# commonBoard.net
KiCad netlist of a schematic drawn in EAGLE
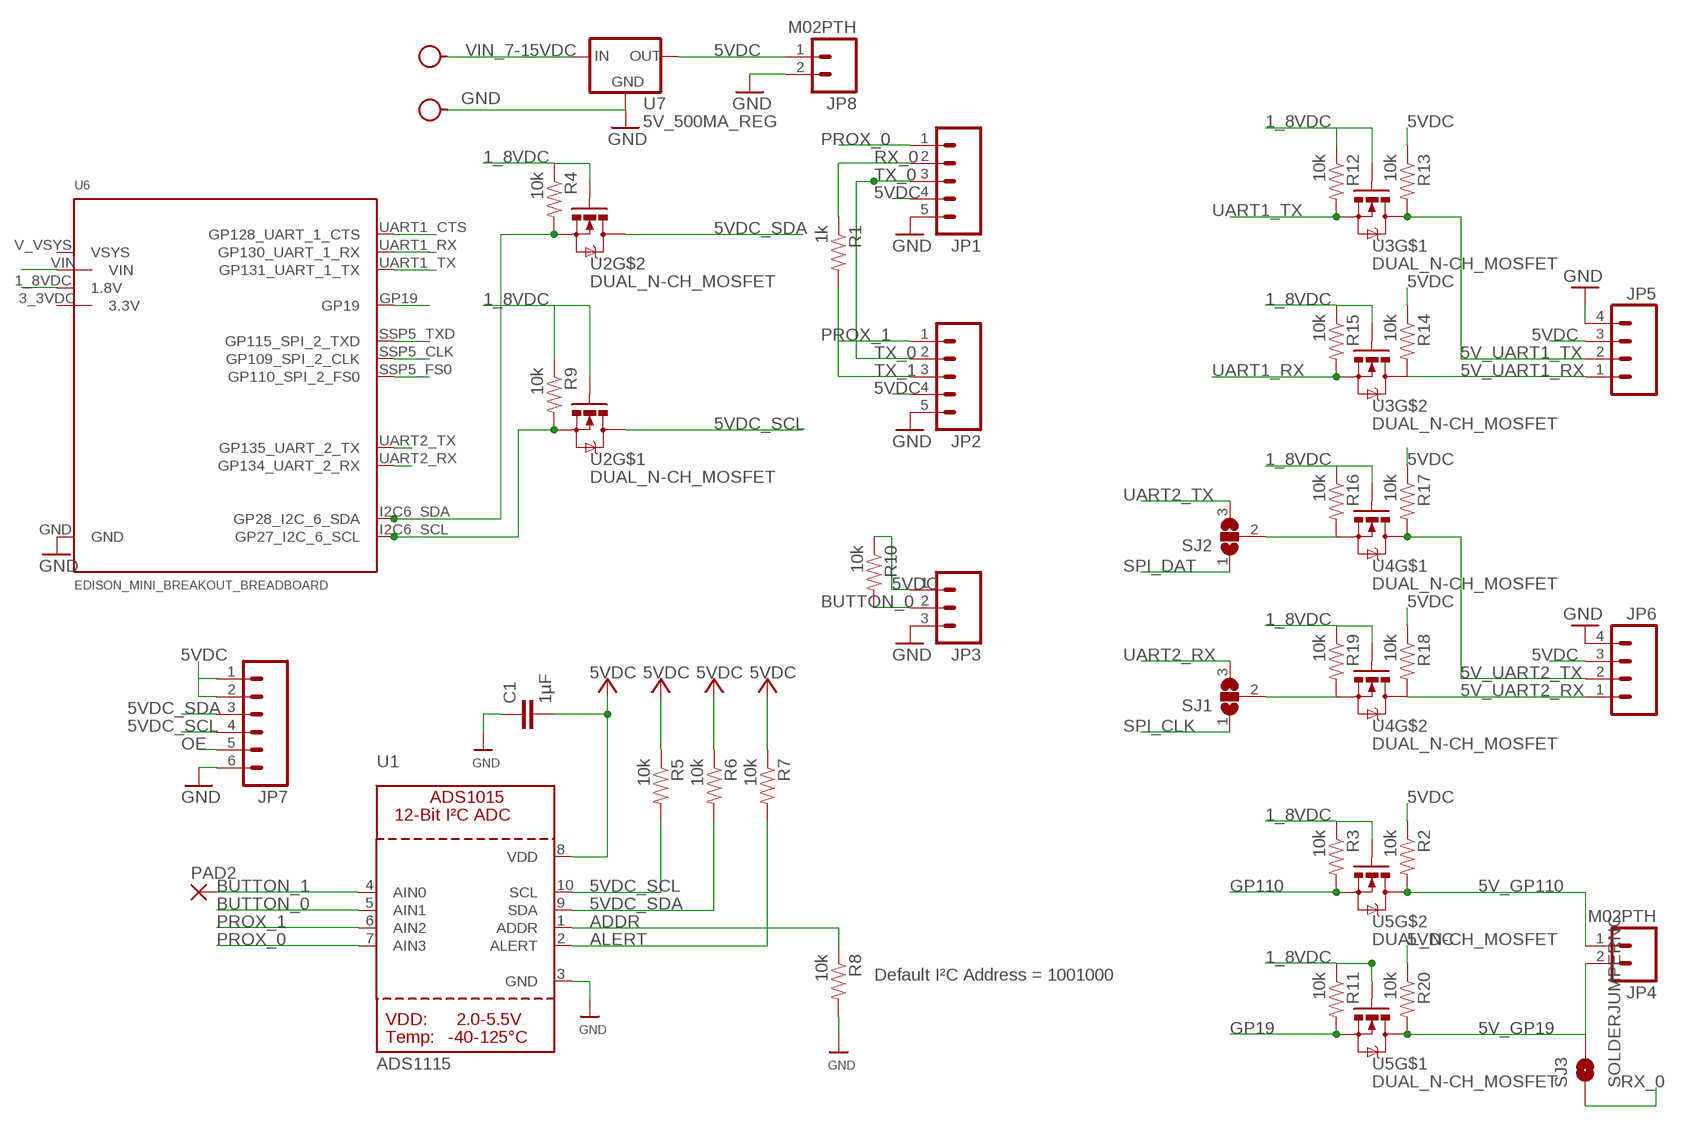
[diagram p0: schematic, sheet 1]

(export (version "E")
  (design (tool "Eeschema 10.0.6"))
  (components
    (comp (ref "C1")
      (value "1µF")
      (footprint "eagle-import:0603-CAP")
      (libsource (lib "eagle-import") (part "CAP0603-CAP"))
    )
    (comp (ref "GND")
      (value "SEW_HOLE-SMALL")
      (footprint "eagle-import:SIMPLE_HOLE_SM")
      (libsource (lib "eagle-import") (part "SEW_HOLE-SMALL"))
    )
    (comp (ref "JP1")
      (value "M05PTH")
      (footprint "eagle-import:1X05")
      (libsource (lib "eagle-import") (part "M05PTH"))
    )
    (comp (ref "JP2")
      (value "M05PTH")
      (footprint "eagle-import:1X05")
      (libsource (lib "eagle-import") (part "M05PTH"))
    )
    (comp (ref "JP3")
      (value "M03PTH")
      (footprint "eagle-import:1X03")
      (libsource (lib "eagle-import") (part "M03PTH"))
    )
    (comp (ref "JP4")
      (value "M02PTH")
      (footprint "eagle-import:1X02")
      (libsource (lib "eagle-import") (part "M02PTH"))
    )
    (comp (ref "JP5")
      (value "M04PTH")
      (footprint "eagle-import:1X04")
      (libsource (lib "eagle-import") (part "M04PTH"))
    )
    (comp (ref "JP6")
      (value "M04PTH")
      (footprint "eagle-import:1X04")
      (libsource (lib "eagle-import") (part "M04PTH"))
    )
    (comp (ref "JP7")
      (value "M06SIP")
      (footprint "eagle-import:1X06")
      (libsource (lib "eagle-import") (part "M06SIP"))
    )
    (comp (ref "JP8")
      (value "M02PTH")
      (footprint "eagle-import:1X02")
      (libsource (lib "eagle-import") (part "M02PTH"))
    )
    (comp (ref "PAD2")
      (value "2,15/1,0")
      (footprint "eagle-import:2,15_1,0")
      (libsource (lib "eagle-import") (part "2,15/1,0"))
    )
    (comp (ref "R1")
      (value "1k")
      (footprint "eagle-import:0603-RES")
      (libsource (lib "eagle-import") (part "RESISTOR0603-RES"))
    )
    (comp (ref "R2")
      (value "10k")
      (footprint "eagle-import:0603-RES")
      (libsource (lib "eagle-import") (part "RESISTOR0603-RES"))
    )
    (comp (ref "R3")
      (value "10k")
      (footprint "eagle-import:0603-RES")
      (libsource (lib "eagle-import") (part "RESISTOR0603-RES"))
    )
    (comp (ref "R4")
      (value "10k")
      (footprint "eagle-import:0603-RES")
      (libsource (lib "eagle-import") (part "RESISTOR0603-RES"))
    )
    (comp (ref "R5")
      (value "10k")
      (footprint "eagle-import:0603-RES")
      (libsource (lib "eagle-import") (part "RESISTOR0603-RES"))
    )
    (comp (ref "R6")
      (value "10k")
      (footprint "eagle-import:0603-RES")
      (libsource (lib "eagle-import") (part "RESISTOR0603-RES"))
    )
    (comp (ref "R7")
      (value "10k")
      (footprint "eagle-import:0603-RES")
      (libsource (lib "eagle-import") (part "RESISTOR0603-RES"))
    )
    (comp (ref "R8")
      (value "10k")
      (footprint "eagle-import:0603-RES")
      (libsource (lib "eagle-import") (part "RESISTOR0603-RES"))
    )
    (comp (ref "R9")
      (value "10k")
      (footprint "eagle-import:0603-RES")
      (libsource (lib "eagle-import") (part "RESISTOR0603-RES"))
    )
    (comp (ref "R10")
      (value "10k")
      (footprint "eagle-import:0603-RES")
      (libsource (lib "eagle-import") (part "RESISTOR0603-RES"))
    )
    (comp (ref "R11")
      (value "10k")
      (footprint "eagle-import:0603-RES")
      (libsource (lib "eagle-import") (part "RESISTOR0603-RES"))
    )
    (comp (ref "R12")
      (value "10k")
      (footprint "eagle-import:0603-RES")
      (libsource (lib "eagle-import") (part "RESISTOR0603-RES"))
    )
    (comp (ref "R13")
      (value "10k")
      (footprint "eagle-import:0603-RES")
      (libsource (lib "eagle-import") (part "RESISTOR0603-RES"))
    )
    (comp (ref "R14")
      (value "10k")
      (footprint "eagle-import:0603-RES")
      (libsource (lib "eagle-import") (part "RESISTOR0603-RES"))
    )
    (comp (ref "R15")
      (value "10k")
      (footprint "eagle-import:0603-RES")
      (libsource (lib "eagle-import") (part "RESISTOR0603-RES"))
    )
    (comp (ref "R16")
      (value "10k")
      (footprint "eagle-import:0603-RES")
      (libsource (lib "eagle-import") (part "RESISTOR0603-RES"))
    )
    (comp (ref "R17")
      (value "10k")
      (footprint "eagle-import:0603-RES")
      (libsource (lib "eagle-import") (part "RESISTOR0603-RES"))
    )
    (comp (ref "R18")
      (value "10k")
      (footprint "eagle-import:0603-RES")
      (libsource (lib "eagle-import") (part "RESISTOR0603-RES"))
    )
    (comp (ref "R19")
      (value "10k")
      (footprint "eagle-import:0603-RES")
      (libsource (lib "eagle-import") (part "RESISTOR0603-RES"))
    )
    (comp (ref "R20")
      (value "10k")
      (footprint "eagle-import:0603-RES")
      (libsource (lib "eagle-import") (part "RESISTOR0603-RES"))
    )
    (comp (ref "SJ1")
      (value "SJ2W")
      (footprint "eagle-import:SJ_2")
      (libsource (lib "eagle-import") (part "SJ2W"))
    )
    (comp (ref "SJ2")
      (value "SJ2W")
      (footprint "eagle-import:SJ_2")
      (libsource (lib "eagle-import") (part "SJ2W"))
    )
    (comp (ref "SJ3")
      (value "SOLDERJUMPERNC")
      (footprint "eagle-import:SJ_2S")
      (libsource (lib "eagle-import") (part "SOLDERJUMPERNC"))
    )
    (comp (ref "U1")
      (value "ADS1115")
      (footprint "eagle-import:MSOP10")
      (libsource (lib "eagle-import") (part "ADC_ADS1015"))
    )
    (comp (ref "U2")
      (value "DUAL_N-CH_MOSFET")
      (footprint "eagle-import:SOT363_DUAL_N_MOSFET")
      (libsource (lib "eagle-import") (part "DUAL_N-CH_MOSFET"))
    )
    (comp (ref "U3")
      (value "DUAL_N-CH_MOSFET")
      (footprint "eagle-import:SOT363_DUAL_N_MOSFET")
      (libsource (lib "eagle-import") (part "DUAL_N-CH_MOSFET"))
    )
    (comp (ref "U4")
      (value "DUAL_N-CH_MOSFET")
      (footprint "eagle-import:SOT363_DUAL_N_MOSFET")
      (libsource (lib "eagle-import") (part "DUAL_N-CH_MOSFET"))
    )
    (comp (ref "U5")
      (value "DUAL_N-CH_MOSFET")
      (footprint "eagle-import:SOT363_DUAL_N_MOSFET")
      (libsource (lib "eagle-import") (part "DUAL_N-CH_MOSFET"))
    )
    (comp (ref "U6")
      (value "EDISON_MINI_BREAKOUT_BREADBOARD")
      (footprint "eagle-import:EDISON_MINI_BREAK_BREADBOARD")
      (libsource (lib "eagle-import") (part "EDISON_MINI_BREAKOUT_BREADBOARD"))
    )
    (comp (ref "U7")
      (value "5V_500MA_REG")
      (footprint "eagle-import:5V_500MA_REG")
      (libsource (lib "eagle-import") (part "5V_500MA_REG"))
    )
    (comp (ref "VIN_7-15VDC")
      (value "SEW_HOLE-SMALL")
      (footprint "eagle-import:SIMPLE_HOLE_SM")
      (libsource (lib "eagle-import") (part "SEW_HOLE-SMALL"))
    )
  )
  (nets
    (net (code "1") (name "/1_8VDC") (class "Default")
      (node (ref "R11") (pin "1") (pinfunction "1_1") (pintype "passive"))
      (node (ref "R12") (pin "1") (pinfunction "1_1") (pintype "passive"))
      (node (ref "R15") (pin "1") (pinfunction "1_1") (pintype "passive"))
      (node (ref "R16") (pin "1") (pinfunction "1_1") (pintype "passive"))
      (node (ref "R19") (pin "1") (pinfunction "1_1") (pintype "passive"))
      (node (ref "R3") (pin "1") (pinfunction "1_1") (pintype "passive"))
      (node (ref "R4") (pin "1") (pinfunction "1_1") (pintype "passive"))
      (node (ref "R9") (pin "1") (pinfunction "1_1") (pintype "passive"))
      (node (ref "U2") (pin "2") (pinfunction "G_2") (pintype "passive"))
      (node (ref "U2") (pin "5") (pinfunction "G_5") (pintype "passive"))
      (node (ref "U3") (pin "2") (pinfunction "G_2") (pintype "passive"))
      (node (ref "U3") (pin "5") (pinfunction "G_5") (pintype "passive"))
      (node (ref "U4") (pin "2") (pinfunction "G_2") (pintype "passive"))
      (node (ref "U4") (pin "5") (pinfunction "G_5") (pintype "passive"))
      (node (ref "U5") (pin "2") (pinfunction "G_2") (pintype "passive"))
      (node (ref "U5") (pin "5") (pinfunction "G_5") (pintype "passive"))
      (node (ref "U6") (pin "1_8VDC") (pinfunction "1.8V_1_8VDC") (pintype "bidirectional"))
    )
    (net (code "2") (name "/5VDC_SCL") (class "Default")
      (node (ref "JP7") (pin "4") (pinfunction "4_4") (pintype "passive"))
      (node (ref "R5") (pin "2") (pinfunction "2_2") (pintype "passive"))
      (node (ref "U1") (pin "10") (pinfunction "SCL_10") (pintype "bidirectional"))
      (node (ref "U2") (pin "3") (pinfunction "D_3") (pintype "passive"))
    )
    (net (code "3") (name "/5VDC_SDA") (class "Default")
      (node (ref "JP7") (pin "3") (pinfunction "3_3") (pintype "passive"))
      (node (ref "R6") (pin "2") (pinfunction "2_2") (pintype "passive"))
      (node (ref "U1") (pin "9") (pinfunction "SDA_9") (pintype "bidirectional"))
      (node (ref "U2") (pin "6") (pinfunction "D_6") (pintype "passive"))
    )
    (net (code "4") (name "/5V_GP19") (class "Default")
      (node (ref "JP4") (pin "2") (pinfunction "2_2") (pintype "passive"))
      (node (ref "R20") (pin "2") (pinfunction "2_2") (pintype "passive"))
      (node (ref "SJ3") (pin "2") (pinfunction "2_2") (pintype "passive"))
      (node (ref "U5") (pin "3") (pinfunction "D_3") (pintype "passive"))
    )
    (net (code "5") (name "/5V_GP110") (class "Default")
      (node (ref "JP4") (pin "1") (pinfunction "1_1") (pintype "passive"))
      (node (ref "R2") (pin "2") (pinfunction "2_2") (pintype "passive"))
      (node (ref "U5") (pin "6") (pinfunction "D_6") (pintype "passive"))
    )
    (net (code "6") (name "/5V_UART1_RX") (class "Default")
      (node (ref "JP5") (pin "1") (pinfunction "1_1") (pintype "passive"))
      (node (ref "R14") (pin "2") (pinfunction "2_2") (pintype "passive"))
      (node (ref "U3") (pin "6") (pinfunction "D_6") (pintype "passive"))
    )
    (net (code "7") (name "/5V_UART1_TX") (class "Default")
      (node (ref "JP5") (pin "2") (pinfunction "2_2") (pintype "passive"))
      (node (ref "R13") (pin "2") (pinfunction "2_2") (pintype "passive"))
      (node (ref "U3") (pin "3") (pinfunction "D_3") (pintype "passive"))
    )
    (net (code "8") (name "/5V_UART2_RX") (class "Default")
      (node (ref "JP6") (pin "1") (pinfunction "1_1") (pintype "passive"))
      (node (ref "R18") (pin "2") (pinfunction "2_2") (pintype "passive"))
      (node (ref "U4") (pin "6") (pinfunction "D_6") (pintype "passive"))
    )
    (net (code "9") (name "/5V_UART2_TX") (class "Default")
      (node (ref "JP6") (pin "2") (pinfunction "2_2") (pintype "passive"))
      (node (ref "R17") (pin "2") (pinfunction "2_2") (pintype "passive"))
      (node (ref "U4") (pin "3") (pinfunction "D_3") (pintype "passive"))
    )
    (net (code "10") (name "/ADDR") (class "Default")
      (node (ref "R8") (pin "1") (pinfunction "1_1") (pintype "passive"))
      (node (ref "U1") (pin "1") (pinfunction "ADDR_1") (pintype "bidirectional"))
    )
    (net (code "11") (name "/ALERT") (class "Default")
      (node (ref "R7") (pin "2") (pinfunction "2_2") (pintype "passive"))
      (node (ref "U1") (pin "2") (pinfunction "ALERT_2") (pintype "bidirectional"))
    )
    (net (code "12") (name "/BUTTON_0") (class "Default")
      (node (ref "JP3") (pin "2") (pinfunction "2_2") (pintype "passive"))
      (node (ref "R10") (pin "2") (pinfunction "2_2") (pintype "passive"))
      (node (ref "U1") (pin "5") (pinfunction "AIN1_5") (pintype "bidirectional"))
    )
    (net (code "13") (name "/BUTTON_1") (class "Default")
      (node (ref "PAD2") (pin "1") (pinfunction "P_1") (pintype "passive"))
      (node (ref "U1") (pin "4") (pinfunction "AIN0_4") (pintype "bidirectional"))
    )
    (net (code "14") (name "/GP19") (class "Default")
      (node (ref "R11") (pin "2") (pinfunction "2_2") (pintype "passive"))
      (node (ref "U5") (pin "4") (pinfunction "S_4") (pintype "passive"))
      (node (ref "U6") (pin "GP19") (pinfunction "GP19_GP19") (pintype "bidirectional"))
    )
    (net (code "15") (name "/GP110") (class "Default")
      (node (ref "R3") (pin "2") (pinfunction "2_2") (pintype "passive"))
      (node (ref "U5") (pin "1") (pinfunction "S_1") (pintype "passive"))
      (node (ref "U6") (pin "SSP5_FS0") (pinfunction "GP110_SPI_2_FS0_SSP5_FS0") (pintype "bidirectional"))
    )
    (net (code "16") (name "/OE") (class "Default")
      (node (ref "JP7") (pin "5") (pinfunction "5_5") (pintype "passive"))
    )
    (net (code "17") (name "/PROX_0") (class "Default")
      (node (ref "JP1") (pin "1") (pinfunction "1_1") (pintype "passive"))
      (node (ref "U1") (pin "7") (pinfunction "AIN3_7") (pintype "bidirectional"))
    )
    (net (code "18") (name "/PROX_1") (class "Default")
      (node (ref "JP2") (pin "1") (pinfunction "1_1") (pintype "passive"))
      (node (ref "U1") (pin "6") (pinfunction "AIN2_6") (pintype "bidirectional"))
    )
    (net (code "19") (name "/RX_0") (class "Default")
      (node (ref "JP1") (pin "2") (pinfunction "2_2") (pintype "passive"))
      (node (ref "R1") (pin "1") (pinfunction "1_1") (pintype "passive"))
      (node (ref "SJ3") (pin "1") (pinfunction "1_1") (pintype "passive"))
    )
    (net (code "20") (name "/SPI_CLK") (class "Default")
      (node (ref "SJ1") (pin "1") (pinfunction "1_1") (pintype "passive"))
      (node (ref "U6") (pin "SSP5_CLK") (pinfunction "GP109_SPI_2_CLK_SSP5_CLK") (pintype "bidirectional"))
    )
    (net (code "21") (name "/SPI_DAT") (class "Default")
      (node (ref "SJ2") (pin "1") (pinfunction "1_1") (pintype "passive"))
      (node (ref "U6") (pin "SSP5_TXD") (pinfunction "GP115_SPI_2_TXD_SSP5_TXD") (pintype "bidirectional"))
    )
    (net (code "22") (name "/TX_0") (class "Default")
      (node (ref "JP1") (pin "3") (pinfunction "3_3") (pintype "passive"))
      (node (ref "JP2") (pin "2") (pinfunction "2_2") (pintype "passive"))
    )
    (net (code "23") (name "/TX_1") (class "Default")
      (node (ref "JP2") (pin "3") (pinfunction "3_3") (pintype "passive"))
      (node (ref "R1") (pin "2") (pinfunction "2_2") (pintype "passive"))
    )
    (net (code "24") (name "/UART1_RX") (class "Default")
      (node (ref "R15") (pin "2") (pinfunction "2_2") (pintype "passive"))
      (node (ref "U3") (pin "1") (pinfunction "S_1") (pintype "passive"))
      (node (ref "U6") (pin "UART1_RX") (pinfunction "GP130_UART_1_RX_UART1_RX") (pintype "bidirectional"))
    )
    (net (code "25") (name "/UART1_TX") (class "Default")
      (node (ref "R12") (pin "2") (pinfunction "2_2") (pintype "passive"))
      (node (ref "U3") (pin "4") (pinfunction "S_4") (pintype "passive"))
      (node (ref "U6") (pin "UART1_TX") (pinfunction "GP131_UART_1_TX_UART1_TX") (pintype "bidirectional"))
    )
    (net (code "26") (name "/UART2_RX") (class "Default")
      (node (ref "SJ1") (pin "3") (pinfunction "3_3") (pintype "passive"))
      (node (ref "U6") (pin "UART2_RX") (pinfunction "GP134_UART_2_RX_UART2_RX") (pintype "bidirectional"))
    )
    (net (code "27") (name "/UART2_TX") (class "Default")
      (node (ref "SJ2") (pin "3") (pinfunction "3_3") (pintype "passive"))
      (node (ref "U6") (pin "UART2_TX") (pinfunction "GP135_UART_2_TX_UART2_TX") (pintype "bidirectional"))
    )
    (net (code "28") (name "/VIN_7-15VDC") (class "Default")
      (node (ref "U6") (pin "VIN") (pinfunction "VIN_VIN") (pintype "bidirectional"))
      (node (ref "U7") (pin "IN") (pinfunction "IN_IN") (pintype "input"))
      (node (ref "VIN_7-15VDC") (pin "P$1") (pinfunction "P$1_P$1") (pintype "bidirectional"))
    )
    (net (code "29") (name "GND") (class "Default")
      (node (ref "C1") (pin "1") (pinfunction "1_1") (pintype "passive"))
      (node (ref "GND") (pin "P$1") (pinfunction "P$1_P$1") (pintype "bidirectional"))
      (node (ref "JP1") (pin "5") (pinfunction "5_5") (pintype "passive"))
      (node (ref "JP2") (pin "5") (pinfunction "5_5") (pintype "passive"))
      (node (ref "JP3") (pin "3") (pinfunction "3_3") (pintype "passive"))
      (node (ref "JP5") (pin "4") (pinfunction "4_4") (pintype "passive"))
      (node (ref "JP6") (pin "4") (pinfunction "4_4") (pintype "passive"))
      (node (ref "JP7") (pin "6") (pinfunction "6_6") (pintype "passive"))
      (node (ref "JP8") (pin "2") (pinfunction "2_2") (pintype "passive"))
      (node (ref "R8") (pin "2") (pinfunction "2_2") (pintype "passive"))
      (node (ref "U1") (pin "3") (pinfunction "GND_3") (pintype "bidirectional"))
      (node (ref "U6") (pin "GND") (pinfunction "GND_GND") (pintype "bidirectional"))
      (node (ref "U7") (pin "GND") (pinfunction "GND_GND") (pintype "input"))
    )
    (net (code "30") (name "Net-(U2A-S)") (class "Default")
      (node (ref "R9") (pin "2") (pinfunction "2_2") (pintype "passive"))
      (node (ref "U2") (pin "4") (pinfunction "S_4") (pintype "passive"))
      (node (ref "U6") (pin "I2C6_SCL") (pinfunction "GP27_I2C_6_SCL_I2C6_SCL") (pintype "bidirectional"))
    )
    (net (code "31") (name "Net-(U2B-S)") (class "Default")
      (node (ref "R4") (pin "2") (pinfunction "2_2") (pintype "passive"))
      (node (ref "U2") (pin "1") (pinfunction "S_1") (pintype "passive"))
      (node (ref "U6") (pin "I2C6_SDA") (pinfunction "GP28_I2C_6_SDA_I2C6_SDA") (pintype "bidirectional"))
    )
    (net (code "32") (name "Net-(U4A-S)") (class "Default")
      (node (ref "R16") (pin "2") (pinfunction "2_2") (pintype "passive"))
      (node (ref "SJ2") (pin "2") (pinfunction "2_2") (pintype "passive"))
      (node (ref "U4") (pin "4") (pinfunction "S_4") (pintype "passive"))
    )
    (net (code "33") (name "Net-(U4B-S)") (class "Default")
      (node (ref "R19") (pin "2") (pinfunction "2_2") (pintype "passive"))
      (node (ref "SJ1") (pin "2") (pinfunction "2_2") (pintype "passive"))
      (node (ref "U4") (pin "1") (pinfunction "S_1") (pintype "passive"))
    )
    (net (code "34") (name "VDD") (class "Default")
      (node (ref "C1") (pin "2") (pinfunction "2_2") (pintype "passive"))
      (node (ref "JP1") (pin "4") (pinfunction "4_4") (pintype "passive"))
      (node (ref "JP2") (pin "4") (pinfunction "4_4") (pintype "passive"))
      (node (ref "JP3") (pin "1") (pinfunction "1_1") (pintype "passive"))
      (node (ref "JP5") (pin "3") (pinfunction "3_3") (pintype "passive"))
      (node (ref "JP6") (pin "3") (pinfunction "3_3") (pintype "passive"))
      (node (ref "JP7") (pin "1") (pinfunction "1_1") (pintype "passive"))
      (node (ref "JP7") (pin "2") (pinfunction "2_2") (pintype "passive"))
      (node (ref "JP8") (pin "1") (pinfunction "1_1") (pintype "passive"))
      (node (ref "R10") (pin "1") (pinfunction "1_1") (pintype "passive"))
      (node (ref "R13") (pin "1") (pinfunction "1_1") (pintype "passive"))
      (node (ref "R14") (pin "1") (pinfunction "1_1") (pintype "passive"))
      (node (ref "R17") (pin "1") (pinfunction "1_1") (pintype "passive"))
      (node (ref "R18") (pin "1") (pinfunction "1_1") (pintype "passive"))
      (node (ref "R2") (pin "1") (pinfunction "1_1") (pintype "passive"))
      (node (ref "R20") (pin "1") (pinfunction "1_1") (pintype "passive"))
      (node (ref "R5") (pin "1") (pinfunction "1_1") (pintype "passive"))
      (node (ref "R6") (pin "1") (pinfunction "1_1") (pintype "passive"))
      (node (ref "R7") (pin "1") (pinfunction "1_1") (pintype "passive"))
      (node (ref "U1") (pin "8") (pinfunction "VDD_8") (pintype "bidirectional"))
      (node (ref "U7") (pin "OUT") (pinfunction "OUT_OUT") (pintype "output"))
    )
    (net (code "35") (name "unconnected-(U6-3.3V-Pad3_3VDC)") (class "Default")
      (node (ref "U6") (pin "3_3VDC") (pinfunction "3.3V_3_3VDC") (pintype "bidirectional"))
    )
    (net (code "36") (name "unconnected-(U6-GP128_UART_1_CTS-PadUART1_CTS)") (class "Default")
      (node (ref "U6") (pin "UART1_CTS") (pinfunction "GP128_UART_1_CTS_UART1_CTS") (pintype "bidirectional"))
    )
    (net (code "37") (name "unconnected-(U6-VSYS-PadV_VSYS)") (class "Default")
      (node (ref "U6") (pin "V_VSYS") (pinfunction "VSYS_V_VSYS") (pintype "bidirectional"))
    )
  )
)
